# MCU.net
KiCad netlist of a schematic drawn in Altium Designer
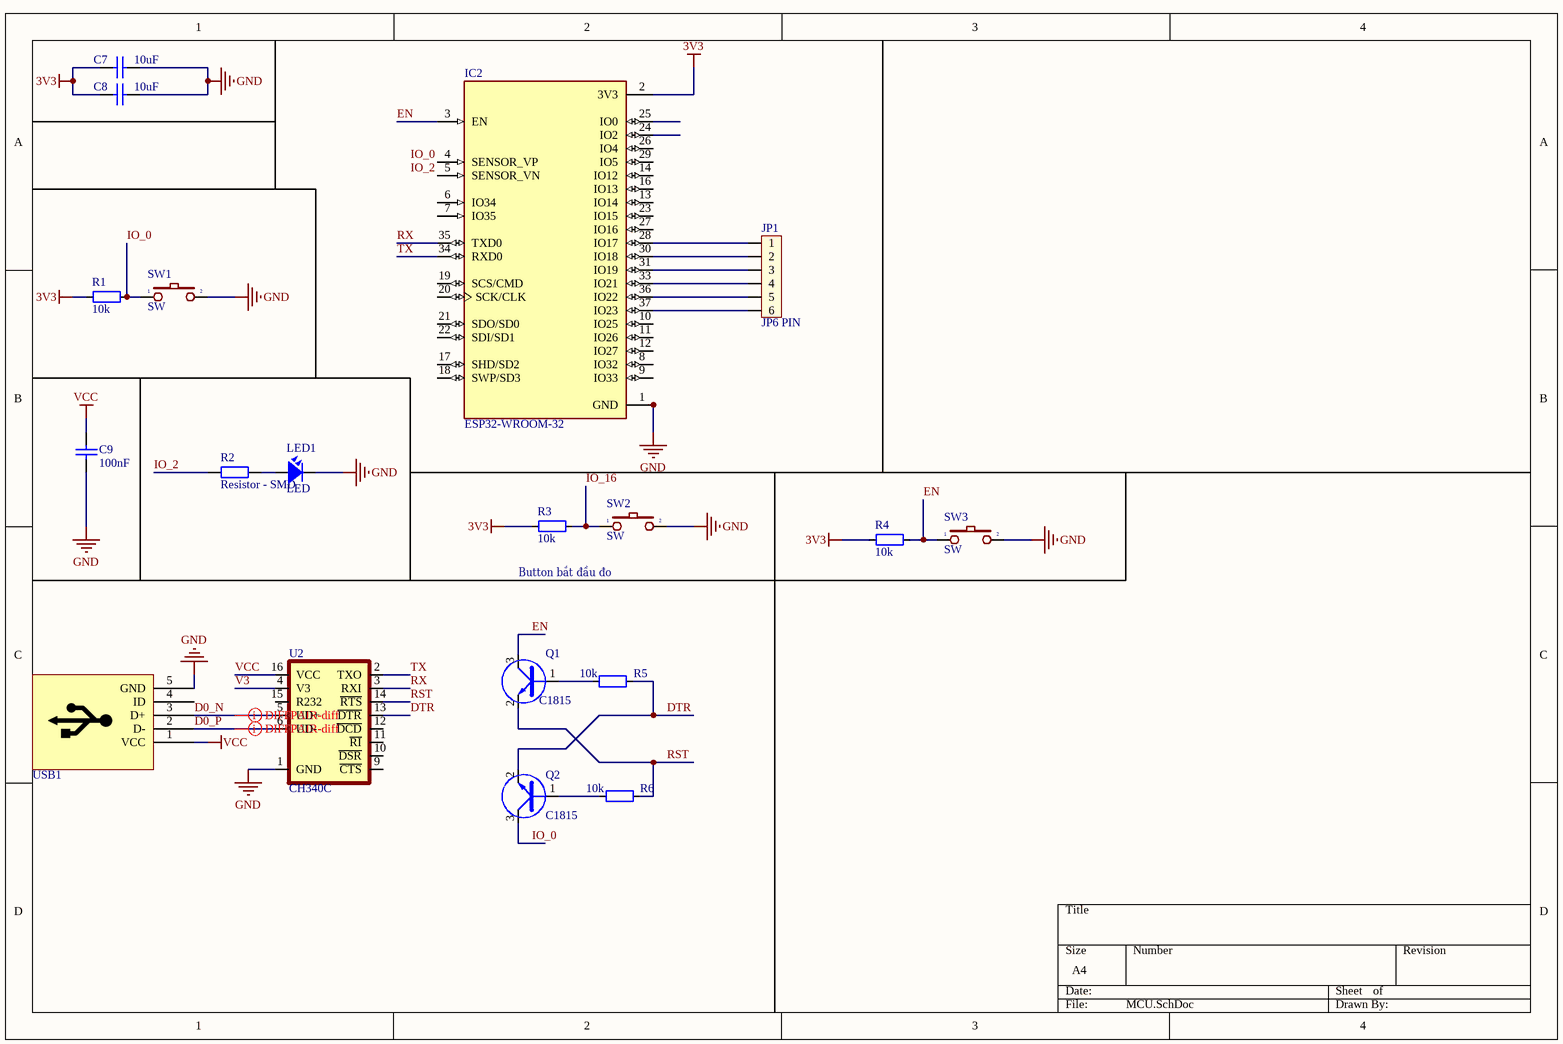
[diagram p0: MCU.SchDoc]

(export (version "E")
  (design (tool "Eeschema 10.0.6"))
  (components
    (comp (ref "C7")
      (value "10uF")
      (footprint "C0805")
      (description "Capacitor")
      (fields (field (name "PUBLISHER") "Altium Limited"))
      (libsource (lib "My Library") (part "CapSMD"))
    )
    (comp (ref "C8")
      (value "10uF")
      (footprint "C0805")
      (description "Capacitor")
      (fields (field (name "PUBLISHER") "Altium Limited"))
      (libsource (lib "My Library") (part "CapSMD"))
    )
    (comp (ref "C9")
      (value "100nF")
      (footprint "C0805")
      (description "Capacitor")
      (fields (field (name "PUBLISHER") "Altium Limited"))
      (libsource (lib "My Library") (part "CapSMD"))
    )
    (comp (ref "IC2")
      (value "ESP32-WROOM-32")
      (footprint "MODULE_ESP32-WROOM-32")
      (description "Bluetooth, WiFi Transceiver Module 2.4GHz ~ 2.5GHz Surface Mount")
      (fields (field (name "MF") "Espressif Systems") (field (name "DIGI-KEY_PART_NUMBER") "1904-1010-1-ND"))
      (libsource (lib "Main") (part "ESP32-WROOM-32"))
    )
    (comp (ref "JP1") (value "JP6 PIN") (footprint "JP6") (libsource (lib "Main") (part "JP6")))
    (comp (ref "LED1")
      (value "LED")
      (footprint "LED0805")
      (description "LED Single colour Green and Red")
      (libsource (lib "Main") (part "LED"))
    )
    (comp (ref "Q1")
      (value "C1815")
      (footprint "SOT23D")
      (description "NPN 600mW, ECB")
      (libsource (lib "My Library") (part "2SC1815"))
    )
    (comp (ref "Q2")
      (value "C1815")
      (footprint "SOT23D")
      (description "NPN 600mW, ECB")
      (libsource (lib "") (part "2SC1815_1"))
    )
    (comp (ref "R1")
      (value "10k")
      (footprint "RES-SMD-0805")
      (description "Resistor")
      (fields
        (field (name "MANUFACTURER") "Generic Components")
        (field (name "PUBLISHER") "Altium Hobart Technology Centre")
      )
      (libsource (lib "My Library") (part "Resistor - SMD"))
    )
    (comp (ref "R2")
      (value "Resistor - SMD")
      (footprint "RES-SMD-0805")
      (description "Resistor SMD")
      (fields
        (field (name "MANUFACTURER") "Generic Components")
        (field (name "PUBLISHER") "Altium Hobart Technology Centre")
      )
      (libsource (lib "Main") (part "Resistor - SMD"))
    )
    (comp (ref "R3")
      (value "10k")
      (footprint "RES-SMD-0805")
      (description "Resistor")
      (fields
        (field (name "MANUFACTURER") "Generic Components")
        (field (name "PUBLISHER") "Altium Hobart Technology Centre")
      )
      (libsource (lib "My Library") (part "Resistor - SMD"))
    )
    (comp (ref "R4")
      (value "10k")
      (footprint "RES-SMD-0805")
      (description "Resistor")
      (fields
        (field (name "MANUFACTURER") "Generic Components")
        (field (name "PUBLISHER") "Altium Hobart Technology Centre")
      )
      (libsource (lib "My Library") (part "Resistor - SMD"))
    )
    (comp (ref "R5")
      (value "10k")
      (footprint "RES-SMD-0805")
      (description "Resistor")
      (fields
        (field (name "MANUFACTURER") "Generic Components")
        (field (name "PUBLISHER") "Altium Hobart Technology Centre")
      )
      (libsource (lib "My Library") (part "Resistor - SMD"))
    )
    (comp (ref "R6")
      (value "10k")
      (footprint "RES-SMD-0805")
      (description "Resistor")
      (fields
        (field (name "MANUFACTURER") "Generic Components")
        (field (name "PUBLISHER") "Altium Hobart Technology Centre")
      )
      (libsource (lib "My Library") (part "Resistor - SMD"))
    )
    (comp (ref "SW1")
      (value "SW")
      (footprint "SW2")
      (description "Switch button 2 pin")
      (libsource (lib "My Library") (part "SW2"))
    )
    (comp (ref "SW2")
      (value "SW")
      (footprint "SW2")
      (description "Switch button 2 pin")
      (libsource (lib "My Library") (part "SW2"))
    )
    (comp (ref "SW3")
      (value "SW")
      (footprint "SW2")
      (description "Switch button 2 pin")
      (libsource (lib "My Library") (part "SW2"))
    )
    (comp (ref "U2")
      (value "CH340C")
      (footprint "SOP-16")
      (description "USB to serial chip CH340")
      (fields (field (name "MF") "WCH"))
      (libsource (lib "My Library") (part "CH340C"))
    )
    (comp (ref "USB1") (value "USB") (footprint "USB-M1") (libsource (lib "My Library") (part "USB-M")))
  )
  (nets
    (net (code "1") (name "/D0_N") (class "Default")
      (node (ref "U2") (pin "5") (pinfunction "UD+_5") (pintype "bidirectional"))
      (node (ref "USB1") (pin "3") (pinfunction "D+_3") (pintype "passive"))
    )
    (net (code "2") (name "/D0_P") (class "Default")
      (node (ref "U2") (pin "6") (pinfunction "UD-_6") (pintype "bidirectional"))
      (node (ref "USB1") (pin "2") (pinfunction "D-_2") (pintype "passive"))
    )
    (net (code "3") (name "/DTR") (class "Default")
      (node (ref "Q2") (pin "2") (pinfunction "E_2") (pintype "passive"))
      (node (ref "R5") (pin "1") (pinfunction "1_1") (pintype "passive"))
      (node (ref "U2") (pin "13") (pinfunction "~{DTR}_13") (pintype "bidirectional"))
    )
    (net (code "4") (name "/EN") (class "Default")
      (node (ref "IC2") (pin "3") (pinfunction "EN_3") (pintype "input"))
      (node (ref "Q1") (pin "3") (pinfunction "C_3") (pintype "passive"))
      (node (ref "R4") (pin "1") (pinfunction "1_1") (pintype "passive"))
      (node (ref "SW3") (pin "1") (pinfunction "1_1") (pintype "passive"))
    )
    (net (code "5") (name "/IO_0") (class "Default")
      (node (ref "Q2") (pin "3") (pinfunction "C_3") (pintype "passive"))
      (node (ref "R1") (pin "1") (pinfunction "1_1") (pintype "passive"))
      (node (ref "SW1") (pin "1") (pinfunction "1_1") (pintype "passive"))
    )
    (net (code "6") (name "/IO_2") (class "Default")
      (node (ref "R2") (pin "2") (pinfunction "2_2") (pintype "passive"))
    )
    (net (code "7") (name "/IO_16") (class "Default")
      (node (ref "R3") (pin "1") (pinfunction "1_1") (pintype "passive"))
      (node (ref "SW2") (pin "1") (pinfunction "1_1") (pintype "passive"))
    )
    (net (code "8") (name "/RST") (class "Default")
      (node (ref "Q1") (pin "2") (pinfunction "E_2") (pintype "passive"))
      (node (ref "R6") (pin "1") (pinfunction "1_1") (pintype "passive"))
      (node (ref "U2") (pin "14") (pinfunction "~{RTS}_14") (pintype "bidirectional"))
    )
    (net (code "9") (name "/RX") (class "Default")
      (node (ref "IC2") (pin "35") (pinfunction "TXD0_35") (pintype "bidirectional"))
      (node (ref "U2") (pin "3") (pinfunction "RXI_3") (pintype "bidirectional"))
    )
    (net (code "10") (name "/TX") (class "Default")
      (node (ref "IC2") (pin "34") (pinfunction "RXD0_34") (pintype "bidirectional"))
      (node (ref "U2") (pin "2") (pinfunction "TXO_2") (pintype "bidirectional"))
    )
    (net (code "11") (name "/V3") (class "Default")
      (node (ref "U2") (pin "4") (pinfunction "V3_4") (pintype "bidirectional"))
    )
    (net (code "12") (name "3V3") (class "Default")
      (node (ref "C7") (pin "1") (pinfunction "1_1") (pintype "passive"))
      (node (ref "C8") (pin "1") (pinfunction "1_1") (pintype "passive"))
      (node (ref "IC2") (pin "2") (pinfunction "3V3_2") (pintype "power_in"))
      (node (ref "R1") (pin "2") (pinfunction "2_2") (pintype "passive"))
      (node (ref "R3") (pin "2") (pinfunction "2_2") (pintype "passive"))
      (node (ref "R4") (pin "2") (pinfunction "2_2") (pintype "passive"))
    )
    (net (code "13") (name "GND") (class "Default")
      (node (ref "C7") (pin "2") (pinfunction "2_2") (pintype "passive"))
      (node (ref "C8") (pin "2") (pinfunction "2_2") (pintype "passive"))
      (node (ref "C9") (pin "1") (pinfunction "1_1") (pintype "passive"))
      (node (ref "IC2") (pin "1") (pinfunction "GND_1") (pintype "power_in"))
      (node (ref "IC2") (pin "15") (pinfunction "GND_15") (pintype "power_in"))
      (node (ref "IC2") (pin "38") (pinfunction "GND_38") (pintype "power_in"))
      (node (ref "IC2") (pin "39_1") (pinfunction "GND_39_1") (pintype "power_in"))
      (node (ref "IC2") (pin "39_10") (pinfunction "GND_39_10") (pintype "power_in"))
      (node (ref "IC2") (pin "39_11") (pinfunction "GND_39_11") (pintype "power_in"))
      (node (ref "IC2") (pin "39_12") (pinfunction "GND_39_12") (pintype "power_in"))
      (node (ref "IC2") (pin "39_13") (pinfunction "GND_39_13") (pintype "power_in"))
      (node (ref "IC2") (pin "39_14") (pinfunction "GND_39_14") (pintype "power_in"))
      (node (ref "IC2") (pin "39_15") (pinfunction "GND_39_15") (pintype "power_in"))
      (node (ref "IC2") (pin "39_16") (pinfunction "GND_39_16") (pintype "power_in"))
      (node (ref "IC2") (pin "39_17") (pinfunction "GND_39_17") (pintype "power_in"))
      (node (ref "IC2") (pin "39_18") (pinfunction "GND_39_18") (pintype "power_in"))
      (node (ref "IC2") (pin "39_19") (pinfunction "GND_39_19") (pintype "power_in"))
      (node (ref "IC2") (pin "39_2") (pinfunction "GND_39_2") (pintype "power_in"))
      (node (ref "IC2") (pin "39_20") (pinfunction "GND_39_20") (pintype "power_in"))
      (node (ref "IC2") (pin "39_21") (pinfunction "GND_39_21") (pintype "power_in"))
      (node (ref "IC2") (pin "39_3") (pinfunction "GND_39_3") (pintype "power_in"))
      (node (ref "IC2") (pin "39_4") (pinfunction "GND_39_4") (pintype "power_in"))
      (node (ref "IC2") (pin "39_5") (pinfunction "GND_39_5") (pintype "power_in"))
      (node (ref "IC2") (pin "39_6") (pinfunction "GND_39_6") (pintype "power_in"))
      (node (ref "IC2") (pin "39_7") (pinfunction "GND_39_7") (pintype "power_in"))
      (node (ref "IC2") (pin "39_8") (pinfunction "GND_39_8") (pintype "power_in"))
      (node (ref "IC2") (pin "39_9") (pinfunction "GND_39_9") (pintype "power_in"))
      (node (ref "LED1") (pin "2") (pinfunction "2_2") (pintype "passive"))
      (node (ref "SW1") (pin "2") (pinfunction "2_2") (pintype "passive"))
      (node (ref "SW2") (pin "2") (pinfunction "2_2") (pintype "passive"))
      (node (ref "SW3") (pin "2") (pinfunction "2_2") (pintype "passive"))
      (node (ref "U2") (pin "1") (pinfunction "GND_1") (pintype "bidirectional"))
      (node (ref "USB1") (pin "5") (pinfunction "GND_5") (pintype "passive"))
    )
    (net (code "14") (name "Net-(IC2-IO17)") (class "Default")
      (node (ref "IC2") (pin "28") (pinfunction "IO17_28") (pintype "bidirectional"))
      (node (ref "JP1") (pin "1") (pinfunction "1_1") (pintype "passive"))
    )
    (net (code "15") (name "Net-(IC2-IO18)") (class "Default")
      (node (ref "IC2") (pin "30") (pinfunction "IO18_30") (pintype "bidirectional"))
      (node (ref "JP1") (pin "2") (pinfunction "2_2") (pintype "passive"))
    )
    (net (code "16") (name "Net-(IC2-IO19)") (class "Default")
      (node (ref "IC2") (pin "31") (pinfunction "IO19_31") (pintype "bidirectional"))
      (node (ref "JP1") (pin "3") (pinfunction "3_3") (pintype "passive"))
    )
    (net (code "17") (name "Net-(IC2-IO21)") (class "Default")
      (node (ref "IC2") (pin "33") (pinfunction "IO21_33") (pintype "bidirectional"))
      (node (ref "JP1") (pin "4") (pinfunction "4_4") (pintype "passive"))
    )
    (net (code "18") (name "Net-(IC2-IO22)") (class "Default")
      (node (ref "IC2") (pin "36") (pinfunction "IO22_36") (pintype "bidirectional"))
      (node (ref "JP1") (pin "5") (pinfunction "5_5") (pintype "passive"))
    )
    (net (code "19") (name "Net-(IC2-IO23)") (class "Default")
      (node (ref "IC2") (pin "37") (pinfunction "IO23_37") (pintype "bidirectional"))
      (node (ref "JP1") (pin "6") (pinfunction "6_6") (pintype "passive"))
    )
    (net (code "20") (name "Net-(LED1-Pad1)") (class "Default")
      (node (ref "LED1") (pin "1") (pinfunction "1_1") (pintype "passive"))
      (node (ref "R2") (pin "1") (pinfunction "1_1") (pintype "passive"))
    )
    (net (code "21") (name "Net-(Q1-B)") (class "Default")
      (node (ref "Q1") (pin "1") (pinfunction "B_1") (pintype "passive"))
      (node (ref "R5") (pin "2") (pinfunction "2_2") (pintype "passive"))
    )
    (net (code "22") (name "Net-(Q2-B)") (class "Default")
      (node (ref "Q2") (pin "1") (pinfunction "B_1") (pintype "passive"))
      (node (ref "R6") (pin "2") (pinfunction "2_2") (pintype "passive"))
    )
    (net (code "23") (name "VCC") (class "Default")
      (node (ref "C9") (pin "2") (pinfunction "2_2") (pintype "passive"))
      (node (ref "U2") (pin "16") (pinfunction "VCC_16") (pintype "bidirectional"))
      (node (ref "USB1") (pin "1") (pinfunction "VCC_1") (pintype "passive"))
    )
    (net (code "24") (name "unconnected-(IC2-IO0-Pad25)") (class "Default")
      (node (ref "IC2") (pin "25") (pinfunction "IO0_25") (pintype "bidirectional"))
    )
    (net (code "25") (name "unconnected-(IC2-IO2-Pad24)") (class "Default")
      (node (ref "IC2") (pin "24") (pinfunction "IO2_24") (pintype "bidirectional"))
    )
    (net (code "26") (name "unconnected-(IC2-IO4-Pad26)") (class "Default")
      (node (ref "IC2") (pin "26") (pinfunction "IO4_26") (pintype "bidirectional"))
    )
    (net (code "27") (name "unconnected-(IC2-IO5-Pad29)") (class "Default")
      (node (ref "IC2") (pin "29") (pinfunction "IO5_29") (pintype "bidirectional"))
    )
    (net (code "28") (name "unconnected-(IC2-IO12-Pad14)") (class "Default")
      (node (ref "IC2") (pin "14") (pinfunction "IO12_14") (pintype "bidirectional"))
    )
    (net (code "29") (name "unconnected-(IC2-IO13-Pad16)") (class "Default")
      (node (ref "IC2") (pin "16") (pinfunction "IO13_16") (pintype "bidirectional"))
    )
    (net (code "30") (name "unconnected-(IC2-IO14-Pad13)") (class "Default")
      (node (ref "IC2") (pin "13") (pinfunction "IO14_13") (pintype "bidirectional"))
    )
    (net (code "31") (name "unconnected-(IC2-IO15-Pad23)") (class "Default")
      (node (ref "IC2") (pin "23") (pinfunction "IO15_23") (pintype "bidirectional"))
    )
    (net (code "32") (name "unconnected-(IC2-IO16-Pad27)") (class "Default")
      (node (ref "IC2") (pin "27") (pinfunction "IO16_27") (pintype "bidirectional"))
    )
    (net (code "33") (name "unconnected-(IC2-IO25-Pad10)") (class "Default")
      (node (ref "IC2") (pin "10") (pinfunction "IO25_10") (pintype "bidirectional"))
    )
    (net (code "34") (name "unconnected-(IC2-IO26-Pad11)") (class "Default")
      (node (ref "IC2") (pin "11") (pinfunction "IO26_11") (pintype "bidirectional"))
    )
    (net (code "35") (name "unconnected-(IC2-IO27-Pad12)") (class "Default")
      (node (ref "IC2") (pin "12") (pinfunction "IO27_12") (pintype "bidirectional"))
    )
    (net (code "36") (name "unconnected-(IC2-IO32-Pad8)") (class "Default")
      (node (ref "IC2") (pin "8") (pinfunction "IO32_8") (pintype "bidirectional"))
    )
    (net (code "37") (name "unconnected-(IC2-IO33-Pad9)") (class "Default")
      (node (ref "IC2") (pin "9") (pinfunction "IO33_9") (pintype "bidirectional"))
    )
    (net (code "38") (name "unconnected-(IC2-IO34-Pad6)") (class "Default")
      (node (ref "IC2") (pin "6") (pinfunction "IO34_6") (pintype "input"))
    )
    (net (code "39") (name "unconnected-(IC2-IO35-Pad7)") (class "Default")
      (node (ref "IC2") (pin "7") (pinfunction "IO35_7") (pintype "input"))
    )
    (net (code "40") (name "unconnected-(IC2-SCK{slash}CLK-Pad20)") (class "Default")
      (node (ref "IC2") (pin "20") (pinfunction "SCK/CLK_20") (pintype "bidirectional"))
    )
    (net (code "41") (name "unconnected-(IC2-SCS{slash}CMD-Pad19)") (class "Default")
      (node (ref "IC2") (pin "19") (pinfunction "SCS/CMD_19") (pintype "bidirectional"))
    )
    (net (code "42") (name "unconnected-(IC2-SDI{slash}SD1-Pad22)") (class "Default")
      (node (ref "IC2") (pin "22") (pinfunction "SDI/SD1_22") (pintype "bidirectional"))
    )
    (net (code "43") (name "unconnected-(IC2-SDO{slash}SD0-Pad21)") (class "Default")
      (node (ref "IC2") (pin "21") (pinfunction "SDO/SD0_21") (pintype "bidirectional"))
    )
    (net (code "44") (name "unconnected-(IC2-SENSOR_VN-Pad5)") (class "Default")
      (node (ref "IC2") (pin "5") (pinfunction "SENSOR_VN_5") (pintype "input"))
    )
    (net (code "45") (name "unconnected-(IC2-SENSOR_VP-Pad4)") (class "Default")
      (node (ref "IC2") (pin "4") (pinfunction "SENSOR_VP_4") (pintype "input"))
    )
    (net (code "46") (name "unconnected-(IC2-SHD{slash}SD2-Pad17)") (class "Default")
      (node (ref "IC2") (pin "17") (pinfunction "SHD/SD2_17") (pintype "bidirectional"))
    )
    (net (code "47") (name "unconnected-(IC2-SWP{slash}SD3-Pad18)") (class "Default")
      (node (ref "IC2") (pin "18") (pinfunction "SWP/SD3_18") (pintype "bidirectional"))
    )
    (net (code "48") (name "unconnected-(U2-R232-Pad15)") (class "Default")
      (node (ref "U2") (pin "15") (pinfunction "R232_15") (pintype "bidirectional"))
    )
    (net (code "49") (name "unconnected-(U2-~{CTS}-Pad9)") (class "Default")
      (node (ref "U2") (pin "9") (pinfunction "~{CTS}_9") (pintype "bidirectional"))
    )
    (net (code "50") (name "unconnected-(U2-~{DCD}-Pad12)") (class "Default")
      (node (ref "U2") (pin "12") (pinfunction "~{DCD}_12") (pintype "bidirectional"))
    )
    (net (code "51") (name "unconnected-(U2-~{DSR}-Pad10)") (class "Default")
      (node (ref "U2") (pin "10") (pinfunction "~{DSR}_10") (pintype "bidirectional"))
    )
    (net (code "52") (name "unconnected-(U2-~{RI}-Pad11)") (class "Default")
      (node (ref "U2") (pin "11") (pinfunction "~{RI}_11") (pintype "bidirectional"))
    )
    (net (code "53") (name "unconnected-(USB1-ID-Pad4)") (class "Default")
      (node (ref "USB1") (pin "4") (pinfunction "ID_4") (pintype "passive"))
    )
  )
)
